# LT3042_15V.net
KiCad netlist of a schematic drawn in Altium Designer
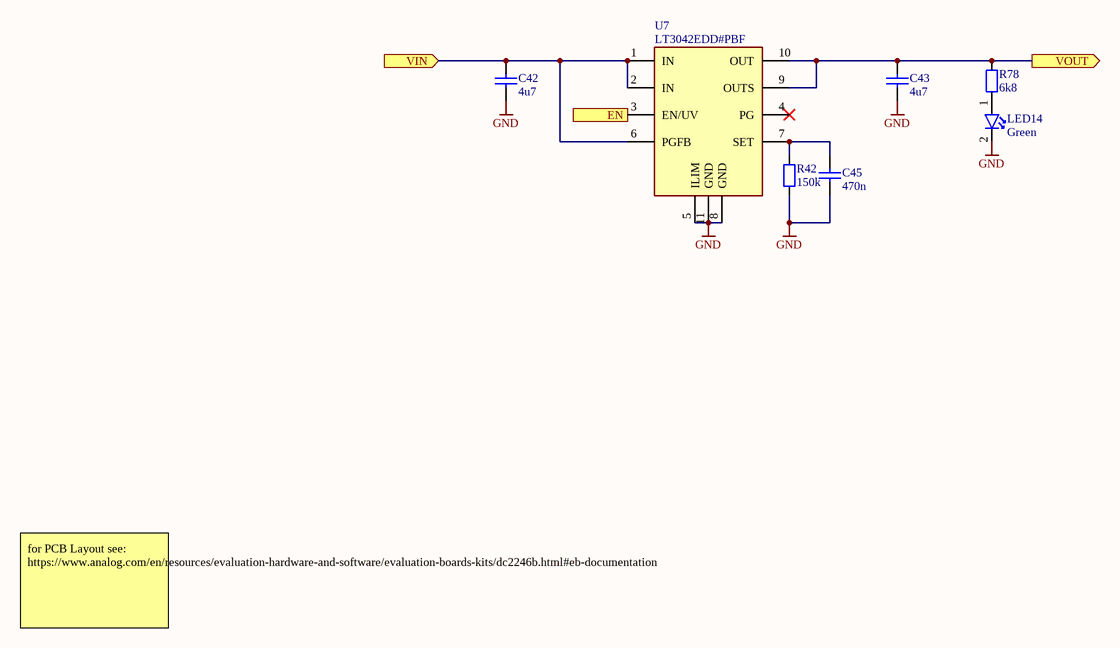
[diagram p0: LT3042_15V.SchDoc]

(export (version "E")
  (design (tool "Eeschema 10.0.6"))
  (components
    (comp (ref "C42")
      (value "4u7")
      (footprint "C_1206_3216Metric_IPC_N")
      (description "Generic MLCC with 1206 Footprint")
      (libsource (lib "database_library") (part "Capacitor_unpol"))
    )
    (comp (ref "C43")
      (value "4u7")
      (footprint "C_1206_3216Metric_IPC_N")
      (description "Generic MLCC with 1206 Footprint")
      (libsource (lib "database_library") (part "Capacitor_unpol"))
    )
    (comp (ref "C45")
      (value "470n")
      (footprint "C_0402_1005Metric_IPC_N")
      (description "Generic MLCC with 0402 Footprint")
      (libsource (lib "database_library") (part "Capacitor_unpol"))
    )
    (comp (ref "LED14")
      (value "Green")
      (footprint "LED_0603_1806Metric_IPC_N")
      (description "MLCC, Low Current, Green, 2.2V, 20mA, 0603")
      (fields
        (field (name "MANUFACTURER") "Broadcom / Avago")
        (field (name "MANUFACTURER PART NUMBER") "HSMG-C190")
      )
      (libsource (lib "database_library") (part "LED"))
    )
    (comp (ref "R42")
      (value "150k")
      (footprint "R_0402_1005Metric_IPC_N")
      (description "Generic Chip Resistor with 0402 Footprint")
      (libsource (lib "database_library") (part "Resistor"))
    )
    (comp (ref "R78")
      (value "6k8")
      (footprint "R_0402_1005Metric_IPC_N")
      (description "Generic Chip Resistor with 0402 Footprint")
      (libsource (lib "database_library") (part "Resistor"))
    )
    (comp (ref "U7")
      (value "LT3042EDD#PBF")
      (footprint "DFN10_3x3")
      (fields (field (name "MANUFACTURER") "Analog Devices"))
      (libsource (lib "database_library") (part "LT3042-10"))
    )
  )
  (nets
    (net (code "1") (name "/EN") (class "Default")
      (node (ref "U7") (pin "3") (pinfunction "EN/UV_3") (pintype "passive"))
    )
    (net (code "2") (name "/VIN") (class "Default")
      (node (ref "C42") (pin "2") (pinfunction "2_2") (pintype "passive"))
      (node (ref "U7") (pin "1") (pinfunction "IN_1") (pintype "passive"))
      (node (ref "U7") (pin "2") (pinfunction "IN_2") (pintype "passive"))
      (node (ref "U7") (pin "6") (pinfunction "PGFB_6") (pintype "passive"))
    )
    (net (code "3") (name "/VOUT") (class "Default")
      (node (ref "C43") (pin "2") (pinfunction "2_2") (pintype "passive"))
      (node (ref "R78") (pin "1") (pinfunction "1_1") (pintype "passive"))
      (node (ref "U7") (pin "10") (pinfunction "OUT_10") (pintype "passive"))
      (node (ref "U7") (pin "9") (pinfunction "OUTS_9") (pintype "passive"))
    )
    (net (code "4") (name "GND") (class "Default")
      (node (ref "C42") (pin "1") (pinfunction "1_1") (pintype "passive"))
      (node (ref "C43") (pin "1") (pinfunction "1_1") (pintype "passive"))
      (node (ref "C45") (pin "1") (pinfunction "1_1") (pintype "passive"))
      (node (ref "LED14") (pin "2") (pinfunction "2_2") (pintype "passive"))
      (node (ref "R42") (pin "1") (pinfunction "1_1") (pintype "passive"))
      (node (ref "U7") (pin "11") (pinfunction "GND_11") (pintype "passive"))
      (node (ref "U7") (pin "5") (pinfunction "ILIM_5") (pintype "passive"))
      (node (ref "U7") (pin "8") (pinfunction "GND_8") (pintype "passive"))
    )
    (net (code "5") (name "Net-(LED14-Pad1)") (class "Default")
      (node (ref "LED14") (pin "1") (pinfunction "1_1") (pintype "passive"))
      (node (ref "R78") (pin "2") (pinfunction "2_2") (pintype "passive"))
    )
    (net (code "6") (name "Net-(U7-SET)") (class "Default")
      (node (ref "C45") (pin "2") (pinfunction "2_2") (pintype "passive"))
      (node (ref "R42") (pin "2") (pinfunction "2_2") (pintype "passive"))
      (node (ref "U7") (pin "7") (pinfunction "SET_7") (pintype "passive"))
    )
    (net (code "7") (name "unconnected-(U7-PG-Pad4)") (class "Default")
      (node (ref "U7") (pin "4") (pinfunction "PG_4") (pintype "passive+no_connect"))
    )
  )
)
